# Rainbow_F103C_Sch.net
KiCad netlist of a schematic drawn in Altium Designer
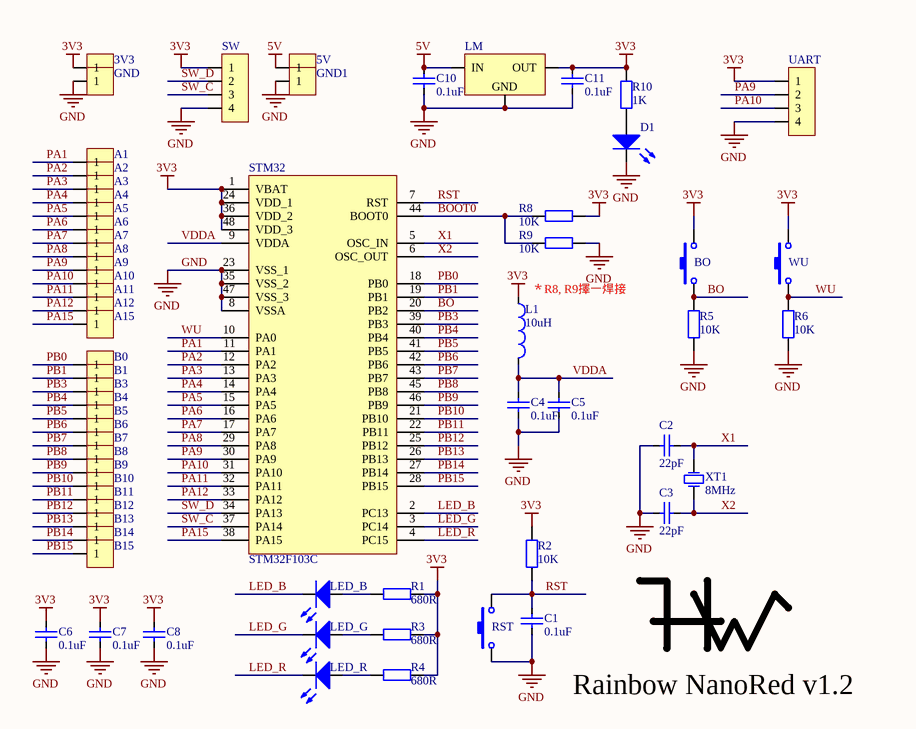
[diagram p0: Rainbow F103C_Sch.SchDoc]

(export (version "E")
  (design (tool "Eeschema 10.0.6"))
  (components
    (comp (ref "3V3")
      (value "HDR1X1_180_2.54")
      (footprint "PCB_Connector:HDR1X1_180_2.54")
      (description "Header")
      (libsource (lib "SCH_Connector") (part "HDR1X1_180_2.54"))
    )
    (comp (ref "5V")
      (value "HDR1X1_180_2.54")
      (footprint "PCB_Connector:HDR1X1_180_2.54")
      (description "Header")
      (libsource (lib "SCH_Connector") (part "HDR1X1_180_2.54"))
    )
    (comp (ref "A1")
      (value "HDR1X1_180_2.54")
      (footprint "PCB_Connector:HDR1X1_180_2.54")
      (description "Header")
      (libsource (lib "SCH_Connector") (part "HDR1X1_180_2.54"))
    )
    (comp (ref "A2")
      (value "HDR1X1_180_2.54")
      (footprint "PCB_Connector:HDR1X1_180_2.54")
      (description "Header")
      (libsource (lib "SCH_Connector") (part "HDR1X1_180_2.54"))
    )
    (comp (ref "A3")
      (value "HDR1X1_180_2.54")
      (footprint "PCB_Connector:HDR1X1_180_2.54")
      (description "Header")
      (libsource (lib "SCH_Connector") (part "HDR1X1_180_2.54"))
    )
    (comp (ref "A4")
      (value "HDR1X1_180_2.54")
      (footprint "PCB_Connector:HDR1X1_180_2.54")
      (description "Header")
      (libsource (lib "SCH_Connector") (part "HDR1X1_180_2.54"))
    )
    (comp (ref "A5")
      (value "HDR1X1_180_2.54")
      (footprint "PCB_Connector:HDR1X1_180_2.54")
      (description "Header")
      (libsource (lib "SCH_Connector") (part "HDR1X1_180_2.54"))
    )
    (comp (ref "A6")
      (value "HDR1X1_180_2.54")
      (footprint "PCB_Connector:HDR1X1_180_2.54")
      (description "Header")
      (libsource (lib "SCH_Connector") (part "HDR1X1_180_2.54"))
    )
    (comp (ref "A7")
      (value "HDR1X1_180_2.54")
      (footprint "PCB_Connector:HDR1X1_180_2.54")
      (description "Header")
      (libsource (lib "SCH_Connector") (part "HDR1X1_180_2.54"))
    )
    (comp (ref "A8")
      (value "HDR1X1_180_2.54")
      (footprint "PCB_Connector:HDR1X1_180_2.54")
      (description "Header")
      (libsource (lib "SCH_Connector") (part "HDR1X1_180_2.54"))
    )
    (comp (ref "A9")
      (value "HDR1X1_180_2.54")
      (footprint "PCB_Connector:HDR1X1_180_2.54")
      (description "Header")
      (libsource (lib "SCH_Connector") (part "HDR1X1_180_2.54"))
    )
    (comp (ref "A10")
      (value "HDR1X1_180_2.54")
      (footprint "PCB_Connector:HDR1X1_180_2.54")
      (description "Header")
      (libsource (lib "SCH_Connector") (part "HDR1X1_180_2.54"))
    )
    (comp (ref "A11")
      (value "HDR1X1_180_2.54")
      (footprint "PCB_Connector:HDR1X1_180_2.54")
      (description "Header")
      (libsource (lib "SCH_Connector") (part "HDR1X1_180_2.54"))
    )
    (comp (ref "A12")
      (value "HDR1X1_180_2.54")
      (footprint "PCB_Connector:HDR1X1_180_2.54")
      (description "Header")
      (libsource (lib "SCH_Connector") (part "HDR1X1_180_2.54"))
    )
    (comp (ref "A15")
      (value "HDR1X1_180_2.54")
      (footprint "PCB_Connector:HDR1X1_180_2.54")
      (description "Header")
      (libsource (lib "SCH_Connector") (part "HDR1X1_180_2.54"))
    )
    (comp (ref "B0")
      (value "HDR1X1_180_2.54")
      (footprint "PCB_Connector:HDR1X1_180_2.54")
      (description "Header")
      (libsource (lib "SCH_Connector") (part "HDR1X1_180_2.54"))
    )
    (comp (ref "B1")
      (value "HDR1X1_180_2.54")
      (footprint "PCB_Connector:HDR1X1_180_2.54")
      (description "Header")
      (libsource (lib "SCH_Connector") (part "HDR1X1_180_2.54"))
    )
    (comp (ref "B3")
      (value "HDR1X1_180_2.54")
      (footprint "PCB_Connector:HDR1X1_180_2.54")
      (description "Header")
      (libsource (lib "SCH_Connector") (part "HDR1X1_180_2.54"))
    )
    (comp (ref "B4")
      (value "HDR1X1_180_2.54")
      (footprint "PCB_Connector:HDR1X1_180_2.54")
      (description "Header")
      (libsource (lib "SCH_Connector") (part "HDR1X1_180_2.54"))
    )
    (comp (ref "B5")
      (value "HDR1X1_180_2.54")
      (footprint "PCB_Connector:HDR1X1_180_2.54")
      (description "Header")
      (libsource (lib "SCH_Connector") (part "HDR1X1_180_2.54"))
    )
    (comp (ref "B6")
      (value "HDR1X1_180_2.54")
      (footprint "PCB_Connector:HDR1X1_180_2.54")
      (description "Header")
      (libsource (lib "SCH_Connector") (part "HDR1X1_180_2.54"))
    )
    (comp (ref "B7")
      (value "HDR1X1_180_2.54")
      (footprint "PCB_Connector:HDR1X1_180_2.54")
      (description "Header")
      (libsource (lib "SCH_Connector") (part "HDR1X1_180_2.54"))
    )
    (comp (ref "B8")
      (value "HDR1X1_180_2.54")
      (footprint "PCB_Connector:HDR1X1_180_2.54")
      (description "Header")
      (libsource (lib "SCH_Connector") (part "HDR1X1_180_2.54"))
    )
    (comp (ref "B9")
      (value "HDR1X1_180_2.54")
      (footprint "PCB_Connector:HDR1X1_180_2.54")
      (description "Header")
      (libsource (lib "SCH_Connector") (part "HDR1X1_180_2.54"))
    )
    (comp (ref "B10")
      (value "HDR1X1_180_2.54")
      (footprint "PCB_Connector:HDR1X1_180_2.54")
      (description "Header")
      (libsource (lib "SCH_Connector") (part "HDR1X1_180_2.54"))
    )
    (comp (ref "B11")
      (value "HDR1X1_180_2.54")
      (footprint "PCB_Connector:HDR1X1_180_2.54")
      (description "Header")
      (libsource (lib "SCH_Connector") (part "HDR1X1_180_2.54"))
    )
    (comp (ref "B12")
      (value "HDR1X1_180_2.54")
      (footprint "PCB_Connector:HDR1X1_180_2.54")
      (description "Header")
      (libsource (lib "SCH_Connector") (part "HDR1X1_180_2.54"))
    )
    (comp (ref "B13")
      (value "HDR1X1_180_2.54")
      (footprint "PCB_Connector:HDR1X1_180_2.54")
      (description "Header")
      (libsource (lib "SCH_Connector") (part "HDR1X1_180_2.54"))
    )
    (comp (ref "B14")
      (value "HDR1X1_180_2.54")
      (footprint "PCB_Connector:HDR1X1_180_2.54")
      (description "Header")
      (libsource (lib "SCH_Connector") (part "HDR1X1_180_2.54"))
    )
    (comp (ref "B15")
      (value "HDR1X1_180_2.54")
      (footprint "PCB_Connector:HDR1X1_180_2.54")
      (description "Header")
      (libsource (lib "SCH_Connector") (part "HDR1X1_180_2.54"))
    )
    (comp (ref "BO")
      (value "BT_TACT_3x6_180")
      (footprint "PCB_Switch:BT_TACT_3x6_180")
      (description "Switch")
      (libsource (lib "SCH_Switch") (part "BT_TACT_3x6_180"))
    )
    (comp (ref "C1")
      (value "0.1uF")
      (footprint "PCB_Passive:CAP_0603")
      (description "Capacitor")
      (fields (field (name "Comment") "Cap_0603"))
      (libsource (lib "SCH_Passive") (part "Cap_0603"))
    )
    (comp (ref "C2")
      (value "22pF")
      (footprint "PCB_Passive:CAP_0603")
      (description "Capacitor")
      (fields (field (name "Comment") "Cap_0603"))
      (libsource (lib "SCH_Passive") (part "Cap_0603"))
    )
    (comp (ref "C3")
      (value "22pF")
      (footprint "PCB_Passive:CAP_0603")
      (description "Capacitor")
      (fields (field (name "Comment") "Cap_0603"))
      (libsource (lib "SCH_Passive") (part "Cap_0603"))
    )
    (comp (ref "C4")
      (value "0.1uF")
      (footprint "PCB_Passive:CAP_0603")
      (description "Capacitor")
      (fields (field (name "Comment") "Cap_0603"))
      (libsource (lib "SCH_Passive") (part "Cap_0603"))
    )
    (comp (ref "C5")
      (value "0.1uF")
      (footprint "PCB_Passive:CAP_0603")
      (description "Capacitor")
      (fields (field (name "Comment") "Cap_0603"))
      (libsource (lib "SCH_Passive") (part "Cap_0603"))
    )
    (comp (ref "C6")
      (value "0.1uF")
      (footprint "PCB_Passive:CAP_0603")
      (description "Capacitor")
      (fields (field (name "Comment") "Cap_0603"))
      (libsource (lib "SCH_Passive") (part "Cap_0603"))
    )
    (comp (ref "C7")
      (value "0.1uF")
      (footprint "PCB_Passive:CAP_0603")
      (description "Capacitor")
      (fields (field (name "Comment") "Cap_0603"))
      (libsource (lib "SCH_Passive") (part "Cap_0603"))
    )
    (comp (ref "C8")
      (value "0.1uF")
      (footprint "PCB_Passive:CAP_0603")
      (description "Capacitor")
      (fields (field (name "Comment") "Cap_0603"))
      (libsource (lib "SCH_Passive") (part "Cap_0603"))
    )
    (comp (ref "C10")
      (value "0.1uF")
      (footprint "PCB_Passive:CAP_0603")
      (description "Capacitor")
      (fields (field (name "Comment") "Cap_0603"))
      (libsource (lib "SCH_Passive") (part "Cap_0603"))
    )
    (comp (ref "C11")
      (value "0.1uF")
      (footprint "PCB_Passive:CAP_0603")
      (description "Capacitor")
      (fields (field (name "Comment") "Cap_0603"))
      (libsource (lib "SCH_Passive") (part "Cap_0603"))
    )
    (comp (ref "D1")
      (value "LED_0603_YELLOW")
      (footprint "PCB_Active:LED_0603_YELLOW")
      (description "LED")
      (libsource (lib "SCH_Active") (part "LED_0603_YELLOW"))
    )
    (comp (ref "GND")
      (value "HDR1X1_180_2.54")
      (footprint "PCB_Connector:HDR1X1_180_2.54")
      (description "Header")
      (libsource (lib "SCH_Connector") (part "HDR1X1_180_2.54"))
    )
    (comp (ref "GND1")
      (value "HDR1X1_180_2.54")
      (footprint "PCB_Connector:HDR1X1_180_2.54")
      (description "Header")
      (libsource (lib "SCH_Connector") (part "HDR1X1_180_2.54"))
    )
    (comp (ref "HW")
      (value "HW")
      (footprint "PCB_Logo:Logo_HW")
      (description "Logo")
      (libsource (lib "SCH_Logo") (part "HW"))
    )
    (comp (ref "L1")
      (value "10uH")
      (footprint "PCB_Passive:IND_0603")
      (description "Inductor")
      (fields (field (name "Comment") "Ind_0603"))
      (libsource (lib "SCH_Passive") (part "Ind_0603"))
    )
    (comp (ref "LED_B")
      (value "LED_0603_BLUE")
      (footprint "PCB_Active:LED_0603_BLUE")
      (description "LED")
      (libsource (lib "SCH_Active") (part "LED_0603_BLUE"))
    )
    (comp (ref "LED_G")
      (value "LED_0603_GREEN")
      (footprint "PCB_Active:LED_0603_GREEN")
      (description "LED")
      (libsource (lib "SCH_Active") (part "LED_0603_GREEN"))
    )
    (comp (ref "LED_R")
      (value "LED_0603_RED")
      (footprint "PCB_Active:LED_0603_RED")
      (description "LED")
      (libsource (lib "SCH_Active") (part "LED_0603_RED"))
    )
    (comp (ref "LM")
      (value "LM1117")
      (footprint "PCB_IC:SOT223")
      (description "Power")
      (libsource (lib "SCH_IC") (part "LM1117"))
    )
    (comp (ref "R1")
      (value "680R")
      (footprint "PCB_Passive:RES_0603")
      (description "Resistor")
      (fields (field (name "Comment") "Res_0603"))
      (libsource (lib "") (part "Res_0603_1"))
    )
    (comp (ref "R2")
      (value "10K")
      (footprint "PCB_Passive:RES_0603")
      (description "Resistor")
      (fields (field (name "Comment") "Res_0603"))
      (libsource (lib "SCH_Passive") (part "Res_0603"))
    )
    (comp (ref "R3")
      (value "680R")
      (footprint "PCB_Passive:RES_0603")
      (description "Resistor")
      (fields (field (name "Comment") "Res_0603"))
      (libsource (lib "") (part "Res_0603_1"))
    )
    (comp (ref "R4")
      (value "680R")
      (footprint "PCB_Passive:RES_0603")
      (description "Resistor")
      (fields (field (name "Comment") "Res_0603"))
      (libsource (lib "") (part "Res_0603_1"))
    )
    (comp (ref "R5")
      (value "10K")
      (footprint "PCB_Passive:RES_0603")
      (description "Resistor")
      (fields (field (name "Comment") "Res_0603"))
      (libsource (lib "SCH_Passive") (part "Res_0603"))
    )
    (comp (ref "R6")
      (value "10K")
      (footprint "PCB_Passive:RES_0603")
      (description "Resistor")
      (fields (field (name "Comment") "Res_0603"))
      (libsource (lib "SCH_Passive") (part "Res_0603"))
    )
    (comp (ref "R8")
      (value "10K")
      (footprint "PCB_Passive:RES_0603")
      (description "Resistor")
      (fields (field (name "Comment") "Res_0603"))
      (libsource (lib "") (part "Res_0603_1"))
    )
    (comp (ref "R9")
      (value "10K")
      (footprint "PCB_Passive:RES_0603")
      (description "Resistor")
      (fields (field (name "Comment") "Res_0603"))
      (libsource (lib "") (part "Res_0603_1"))
    )
    (comp (ref "R10")
      (value "1K")
      (footprint "PCB_Passive:RES_0603")
      (description "Resistor")
      (fields (field (name "Comment") "Res_0603"))
      (libsource (lib "") (part "Res_0603_2"))
    )
    (comp (ref "RST")
      (value "BT_TACT_3x6_180")
      (footprint "PCB_Switch:BT_TACT_3x6_180")
      (description "Switch")
      (libsource (lib "SCH_Switch") (part "BT_TACT_3x6_180"))
    )
    (comp (ref "STM32")
      (value "STM32F103C")
      (footprint "PCB_IC:STM32F_48")
      (description "MCU")
      (libsource (lib "SCH_IC") (part "STM32F103C"))
    )
    (comp (ref "SW")
      (value "HDR1X4_90F_2.54")
      (footprint "PCB_Connector:HDR1X4_90F_2.54")
      (description "Header")
      (libsource (lib "SCH_Connector") (part "HDR1X4_90F_2.54"))
    )
    (comp (ref "UART")
      (value "HDR1X4_90F_2.54")
      (footprint "PCB_Connector:HDR1X4_90F_2.54")
      (description "Header")
      (libsource (lib "SCH_Connector") (part "HDR1X4_90F_2.54"))
    )
    (comp (ref "WU")
      (value "BT_TACT_3x6_180")
      (footprint "PCB_Switch:BT_TACT_3x6_180")
      (description "Switch")
      (libsource (lib "SCH_Switch") (part "BT_TACT_3x6_180"))
    )
    (comp (ref "XT1")
      (value "8MHz")
      (footprint "PCB_Oscillator:XTAL_5032")
      (description "Crystal Oscillator")
      (fields (field (name "Comment") "XTAL_5032") (field (name "PUBLISHER") "Altium Limited"))
      (libsource (lib "SCH_Oscillator") (part "XTAL_5032"))
    )
  )
  (nets
    (net (code "1") (name "/BO") (class "Default")
      (node (ref "BO") (pin "1") (pinfunction "1_1") (pintype "passive"))
      (node (ref "R5") (pin "1") (pinfunction "1_1") (pintype "passive"))
      (node (ref "STM32") (pin "20") (pinfunction "PB2_20") (pintype "passive"))
    )
    (net (code "2") (name "/BOOT0") (class "Default")
      (node (ref "R8") (pin "1") (pinfunction "1_1") (pintype "passive"))
      (node (ref "R9") (pin "1") (pinfunction "1_1") (pintype "passive"))
      (node (ref "STM32") (pin "44") (pinfunction "BOOT0_44") (pintype "passive"))
    )
    (net (code "3") (name "/LED_B") (class "Default")
      (node (ref "LED_B") (pin "2") (pinfunction "K_2") (pintype "passive"))
      (node (ref "STM32") (pin "2") (pinfunction "PC13_2") (pintype "passive"))
    )
    (net (code "4") (name "/LED_G") (class "Default")
      (node (ref "LED_G") (pin "2") (pinfunction "K_2") (pintype "passive"))
      (node (ref "STM32") (pin "3") (pinfunction "PC14_3") (pintype "passive"))
    )
    (net (code "5") (name "/LED_R") (class "Default")
      (node (ref "LED_R") (pin "2") (pinfunction "K_2") (pintype "passive"))
      (node (ref "STM32") (pin "4") (pinfunction "PC15_4") (pintype "passive"))
    )
    (net (code "6") (name "/PA1") (class "Default")
      (node (ref "A1") (pin "1") (pinfunction "1_1") (pintype "passive"))
      (node (ref "STM32") (pin "11") (pinfunction "PA1_11") (pintype "passive"))
    )
    (net (code "7") (name "/PA2") (class "Default")
      (node (ref "A2") (pin "1") (pinfunction "1_1") (pintype "passive"))
      (node (ref "STM32") (pin "12") (pinfunction "PA2_12") (pintype "passive"))
    )
    (net (code "8") (name "/PA3") (class "Default")
      (node (ref "A3") (pin "1") (pinfunction "1_1") (pintype "passive"))
      (node (ref "STM32") (pin "13") (pinfunction "PA3_13") (pintype "passive"))
    )
    (net (code "9") (name "/PA4") (class "Default")
      (node (ref "A4") (pin "1") (pinfunction "1_1") (pintype "passive"))
      (node (ref "STM32") (pin "14") (pinfunction "PA4_14") (pintype "passive"))
    )
    (net (code "10") (name "/PA5") (class "Default")
      (node (ref "A5") (pin "1") (pinfunction "1_1") (pintype "passive"))
      (node (ref "STM32") (pin "15") (pinfunction "PA5_15") (pintype "passive"))
    )
    (net (code "11") (name "/PA6") (class "Default")
      (node (ref "A6") (pin "1") (pinfunction "1_1") (pintype "passive"))
      (node (ref "STM32") (pin "16") (pinfunction "PA6_16") (pintype "passive"))
    )
    (net (code "12") (name "/PA7") (class "Default")
      (node (ref "A7") (pin "1") (pinfunction "1_1") (pintype "passive"))
      (node (ref "STM32") (pin "17") (pinfunction "PA7_17") (pintype "passive"))
    )
    (net (code "13") (name "/PA8") (class "Default")
      (node (ref "A8") (pin "1") (pinfunction "1_1") (pintype "passive"))
      (node (ref "STM32") (pin "29") (pinfunction "PA8_29") (pintype "passive"))
    )
    (net (code "14") (name "/PA9") (class "Default")
      (node (ref "A9") (pin "1") (pinfunction "1_1") (pintype "passive"))
      (node (ref "STM32") (pin "30") (pinfunction "PA9_30") (pintype "passive"))
      (node (ref "UART") (pin "2") (pinfunction "2_2") (pintype "passive"))
    )
    (net (code "15") (name "/PA10") (class "Default")
      (node (ref "A10") (pin "1") (pinfunction "1_1") (pintype "passive"))
      (node (ref "STM32") (pin "31") (pinfunction "PA10_31") (pintype "passive"))
      (node (ref "UART") (pin "3") (pinfunction "3_3") (pintype "passive"))
    )
    (net (code "16") (name "/PA11") (class "Default")
      (node (ref "A11") (pin "1") (pinfunction "1_1") (pintype "passive"))
      (node (ref "STM32") (pin "32") (pinfunction "PA11_32") (pintype "passive"))
    )
    (net (code "17") (name "/PA12") (class "Default")
      (node (ref "A12") (pin "1") (pinfunction "1_1") (pintype "passive"))
      (node (ref "STM32") (pin "33") (pinfunction "PA12_33") (pintype "passive"))
    )
    (net (code "18") (name "/PA15") (class "Default")
      (node (ref "A15") (pin "1") (pinfunction "1_1") (pintype "passive"))
      (node (ref "STM32") (pin "38") (pinfunction "PA15_38") (pintype "passive"))
    )
    (net (code "19") (name "/PB0") (class "Default")
      (node (ref "B0") (pin "1") (pinfunction "1_1") (pintype "passive"))
      (node (ref "STM32") (pin "18") (pinfunction "PB0_18") (pintype "passive"))
    )
    (net (code "20") (name "/PB1") (class "Default")
      (node (ref "B1") (pin "1") (pinfunction "1_1") (pintype "passive"))
      (node (ref "STM32") (pin "19") (pinfunction "PB1_19") (pintype "passive"))
    )
    (net (code "21") (name "/PB3") (class "Default")
      (node (ref "B3") (pin "1") (pinfunction "1_1") (pintype "passive"))
      (node (ref "STM32") (pin "39") (pinfunction "PB3_39") (pintype "passive"))
    )
    (net (code "22") (name "/PB4") (class "Default")
      (node (ref "B4") (pin "1") (pinfunction "1_1") (pintype "passive"))
      (node (ref "STM32") (pin "40") (pinfunction "PB4_40") (pintype "passive"))
    )
    (net (code "23") (name "/PB5") (class "Default")
      (node (ref "B5") (pin "1") (pinfunction "1_1") (pintype "passive"))
      (node (ref "STM32") (pin "41") (pinfunction "PB5_41") (pintype "passive"))
    )
    (net (code "24") (name "/PB6") (class "Default")
      (node (ref "B6") (pin "1") (pinfunction "1_1") (pintype "passive"))
      (node (ref "STM32") (pin "42") (pinfunction "PB6_42") (pintype "passive"))
    )
    (net (code "25") (name "/PB7") (class "Default")
      (node (ref "B7") (pin "1") (pinfunction "1_1") (pintype "passive"))
      (node (ref "STM32") (pin "43") (pinfunction "PB7_43") (pintype "passive"))
    )
    (net (code "26") (name "/PB8") (class "Default")
      (node (ref "B8") (pin "1") (pinfunction "1_1") (pintype "passive"))
      (node (ref "STM32") (pin "45") (pinfunction "PB8_45") (pintype "passive"))
    )
    (net (code "27") (name "/PB9") (class "Default")
      (node (ref "B9") (pin "1") (pinfunction "1_1") (pintype "passive"))
      (node (ref "STM32") (pin "46") (pinfunction "PB9_46") (pintype "passive"))
    )
    (net (code "28") (name "/PB10") (class "Default")
      (node (ref "B10") (pin "1") (pinfunction "1_1") (pintype "passive"))
      (node (ref "STM32") (pin "21") (pinfunction "PB10_21") (pintype "passive"))
    )
    (net (code "29") (name "/PB11") (class "Default")
      (node (ref "B11") (pin "1") (pinfunction "1_1") (pintype "passive"))
      (node (ref "STM32") (pin "22") (pinfunction "PB11_22") (pintype "passive"))
    )
    (net (code "30") (name "/PB12") (class "Default")
      (node (ref "B12") (pin "1") (pinfunction "1_1") (pintype "passive"))
      (node (ref "STM32") (pin "25") (pinfunction "PB12_25") (pintype "passive"))
    )
    (net (code "31") (name "/PB13") (class "Default")
      (node (ref "B13") (pin "1") (pinfunction "1_1") (pintype "passive"))
      (node (ref "STM32") (pin "26") (pinfunction "PB13_26") (pintype "passive"))
    )
    (net (code "32") (name "/PB14") (class "Default")
      (node (ref "B14") (pin "1") (pinfunction "1_1") (pintype "passive"))
      (node (ref "STM32") (pin "27") (pinfunction "PB14_27") (pintype "passive"))
    )
    (net (code "33") (name "/PB15") (class "Default")
      (node (ref "B15") (pin "1") (pinfunction "1_1") (pintype "passive"))
      (node (ref "STM32") (pin "28") (pinfunction "PB15_28") (pintype "passive"))
    )
    (net (code "34") (name "/RST") (class "Default")
      (node (ref "C1") (pin "1") (pinfunction "1_1") (pintype "passive"))
      (node (ref "R2") (pin "2") (pinfunction "2_2") (pintype "passive"))
      (node (ref "RST") (pin "2") (pinfunction "2_2") (pintype "passive"))
      (node (ref "STM32") (pin "7") (pinfunction "RST_7") (pintype "passive"))
    )
    (net (code "35") (name "/SW_C") (class "Default")
      (node (ref "STM32") (pin "37") (pinfunction "PA14_37") (pintype "passive"))
      (node (ref "SW") (pin "3") (pinfunction "3_3") (pintype "passive"))
    )
    (net (code "36") (name "/SW_D") (class "Default")
      (node (ref "STM32") (pin "34") (pinfunction "PA13_34") (pintype "passive"))
      (node (ref "SW") (pin "2") (pinfunction "2_2") (pintype "passive"))
    )
    (net (code "37") (name "/VDDA") (class "Default")
      (node (ref "C4") (pin "2") (pinfunction "2_2") (pintype "passive"))
      (node (ref "C5") (pin "2") (pinfunction "2_2") (pintype "passive"))
      (node (ref "L1") (pin "2") (pinfunction "2_2") (pintype "passive"))
      (node (ref "STM32") (pin "9") (pinfunction "VDDA_9") (pintype "passive"))
    )
    (net (code "38") (name "/WU") (class "Default")
      (node (ref "R6") (pin "1") (pinfunction "1_1") (pintype "passive"))
      (node (ref "STM32") (pin "10") (pinfunction "PA0_10") (pintype "passive"))
      (node (ref "WU") (pin "1") (pinfunction "1_1") (pintype "passive"))
    )
    (net (code "39") (name "/X1") (class "Default")
      (node (ref "C2") (pin "2") (pinfunction "2_2") (pintype "passive"))
      (node (ref "STM32") (pin "5") (pinfunction "OSC_IN_5") (pintype "passive"))
      (node (ref "XT1") (pin "2") (pinfunction "OSC2_2") (pintype "passive"))
    )
    (net (code "40") (name "/X2") (class "Default")
      (node (ref "C3") (pin "2") (pinfunction "2_2") (pintype "passive"))
      (node (ref "STM32") (pin "6") (pinfunction "OSC_OUT_6") (pintype "passive"))
      (node (ref "XT1") (pin "1") (pinfunction "OSC1_1") (pintype "passive"))
    )
    (net (code "41") (name "3V3") (class "Default")
      (node (ref "3V3") (pin "1") (pinfunction "1_1") (pintype "passive"))
      (node (ref "BO") (pin "2") (pinfunction "2_2") (pintype "passive"))
      (node (ref "C11") (pin "2") (pinfunction "2_2") (pintype "passive"))
      (node (ref "C6") (pin "2") (pinfunction "2_2") (pintype "passive"))
      (node (ref "C7") (pin "2") (pinfunction "2_2") (pintype "passive"))
      (node (ref "C8") (pin "2") (pinfunction "2_2") (pintype "passive"))
      (node (ref "L1") (pin "1") (pinfunction "1_1") (pintype "passive"))
      (node (ref "LM") (pin "2") (pinfunction "OUT_2") (pintype "power_in"))
      (node (ref "R1") (pin "2") (pinfunction "2_2") (pintype "passive"))
      (node (ref "R10") (pin "2") (pinfunction "2_2") (pintype "passive"))
      (node (ref "R2") (pin "1") (pinfunction "1_1") (pintype "passive"))
      (node (ref "R3") (pin "2") (pinfunction "2_2") (pintype "passive"))
      (node (ref "R4") (pin "2") (pinfunction "2_2") (pintype "passive"))
      (node (ref "R8") (pin "2") (pinfunction "2_2") (pintype "passive"))
      (node (ref "STM32") (pin "1") (pinfunction "VBAT_1") (pintype "passive"))
      (node (ref "STM32") (pin "24") (pinfunction "VDD_1_24") (pintype "passive"))
      (node (ref "STM32") (pin "36") (pinfunction "VDD_2_36") (pintype "passive"))
      (node (ref "STM32") (pin "48") (pinfunction "VDD_3_48") (pintype "passive"))
      (node (ref "SW") (pin "1") (pinfunction "1_1") (pintype "passive"))
      (node (ref "UART") (pin "1") (pinfunction "1_1") (pintype "passive"))
      (node (ref "WU") (pin "2") (pinfunction "2_2") (pintype "passive"))
    )
    (net (code "42") (name "5V") (class "Default")
      (node (ref "5V") (pin "1") (pinfunction "1_1") (pintype "passive"))
      (node (ref "C10") (pin "2") (pinfunction "2_2") (pintype "passive"))
      (node (ref "LM") (pin "3") (pinfunction "IN_3") (pintype "power_in"))
    )
    (net (code "43") (name "GND") (class "Default")
      (node (ref "C1") (pin "2") (pinfunction "2_2") (pintype "passive"))
      (node (ref "C10") (pin "1") (pinfunction "1_1") (pintype "passive"))
      (node (ref "C11") (pin "1") (pinfunction "1_1") (pintype "passive"))
      (node (ref "C2") (pin "1") (pinfunction "1_1") (pintype "passive"))
      (node (ref "C3") (pin "1") (pinfunction "1_1") (pintype "passive"))
      (node (ref "C4") (pin "1") (pinfunction "1_1") (pintype "passive"))
      (node (ref "C5") (pin "1") (pinfunction "1_1") (pintype "passive"))
      (node (ref "C6") (pin "1") (pinfunction "1_1") (pintype "passive"))
      (node (ref "C7") (pin "1") (pinfunction "1_1") (pintype "passive"))
      (node (ref "C8") (pin "1") (pinfunction "1_1") (pintype "passive"))
      (node (ref "D1") (pin "2") (pinfunction "K_2") (pintype "passive"))
      (node (ref "GND") (pin "1") (pinfunction "1_1") (pintype "passive"))
      (node (ref "GND1") (pin "1") (pinfunction "1_1") (pintype "passive"))
      (node (ref "LM") (pin "1") (pinfunction "GND_1") (pintype "power_in"))
      (node (ref "R5") (pin "2") (pinfunction "2_2") (pintype "passive"))
      (node (ref "R6") (pin "2") (pinfunction "2_2") (pintype "passive"))
      (node (ref "R9") (pin "2") (pinfunction "2_2") (pintype "passive"))
      (node (ref "RST") (pin "1") (pinfunction "1_1") (pintype "passive"))
      (node (ref "STM32") (pin "23") (pinfunction "VSS_1_23") (pintype "passive"))
      (node (ref "STM32") (pin "35") (pinfunction "VSS_2_35") (pintype "passive"))
      (node (ref "STM32") (pin "47") (pinfunction "VSS_3_47") (pintype "passive"))
      (node (ref "STM32") (pin "8") (pinfunction "VSSA_8") (pintype "passive"))
      (node (ref "SW") (pin "4") (pinfunction "4_4") (pintype "passive"))
      (node (ref "UART") (pin "4") (pinfunction "4_4") (pintype "passive"))
    )
    (net (code "44") (name "Net-(D1-A)") (class "Default")
      (node (ref "D1") (pin "1") (pinfunction "A_1") (pintype "passive"))
      (node (ref "R10") (pin "1") (pinfunction "1_1") (pintype "passive"))
    )
    (net (code "45") (name "Net-(LED_B-A)") (class "Default")
      (node (ref "LED_B") (pin "1") (pinfunction "A_1") (pintype "passive"))
      (node (ref "R1") (pin "1") (pinfunction "1_1") (pintype "passive"))
    )
    (net (code "46") (name "Net-(LED_G-A)") (class "Default")
      (node (ref "LED_G") (pin "1") (pinfunction "A_1") (pintype "passive"))
      (node (ref "R3") (pin "1") (pinfunction "1_1") (pintype "passive"))
    )
    (net (code "47") (name "Net-(LED_R-A)") (class "Default")
      (node (ref "LED_R") (pin "1") (pinfunction "A_1") (pintype "passive"))
      (node (ref "R4") (pin "1") (pinfunction "1_1") (pintype "passive"))
    )
  )
)
